# 20ma.net
KiCad netlist of a schematic drawn in EAGLE
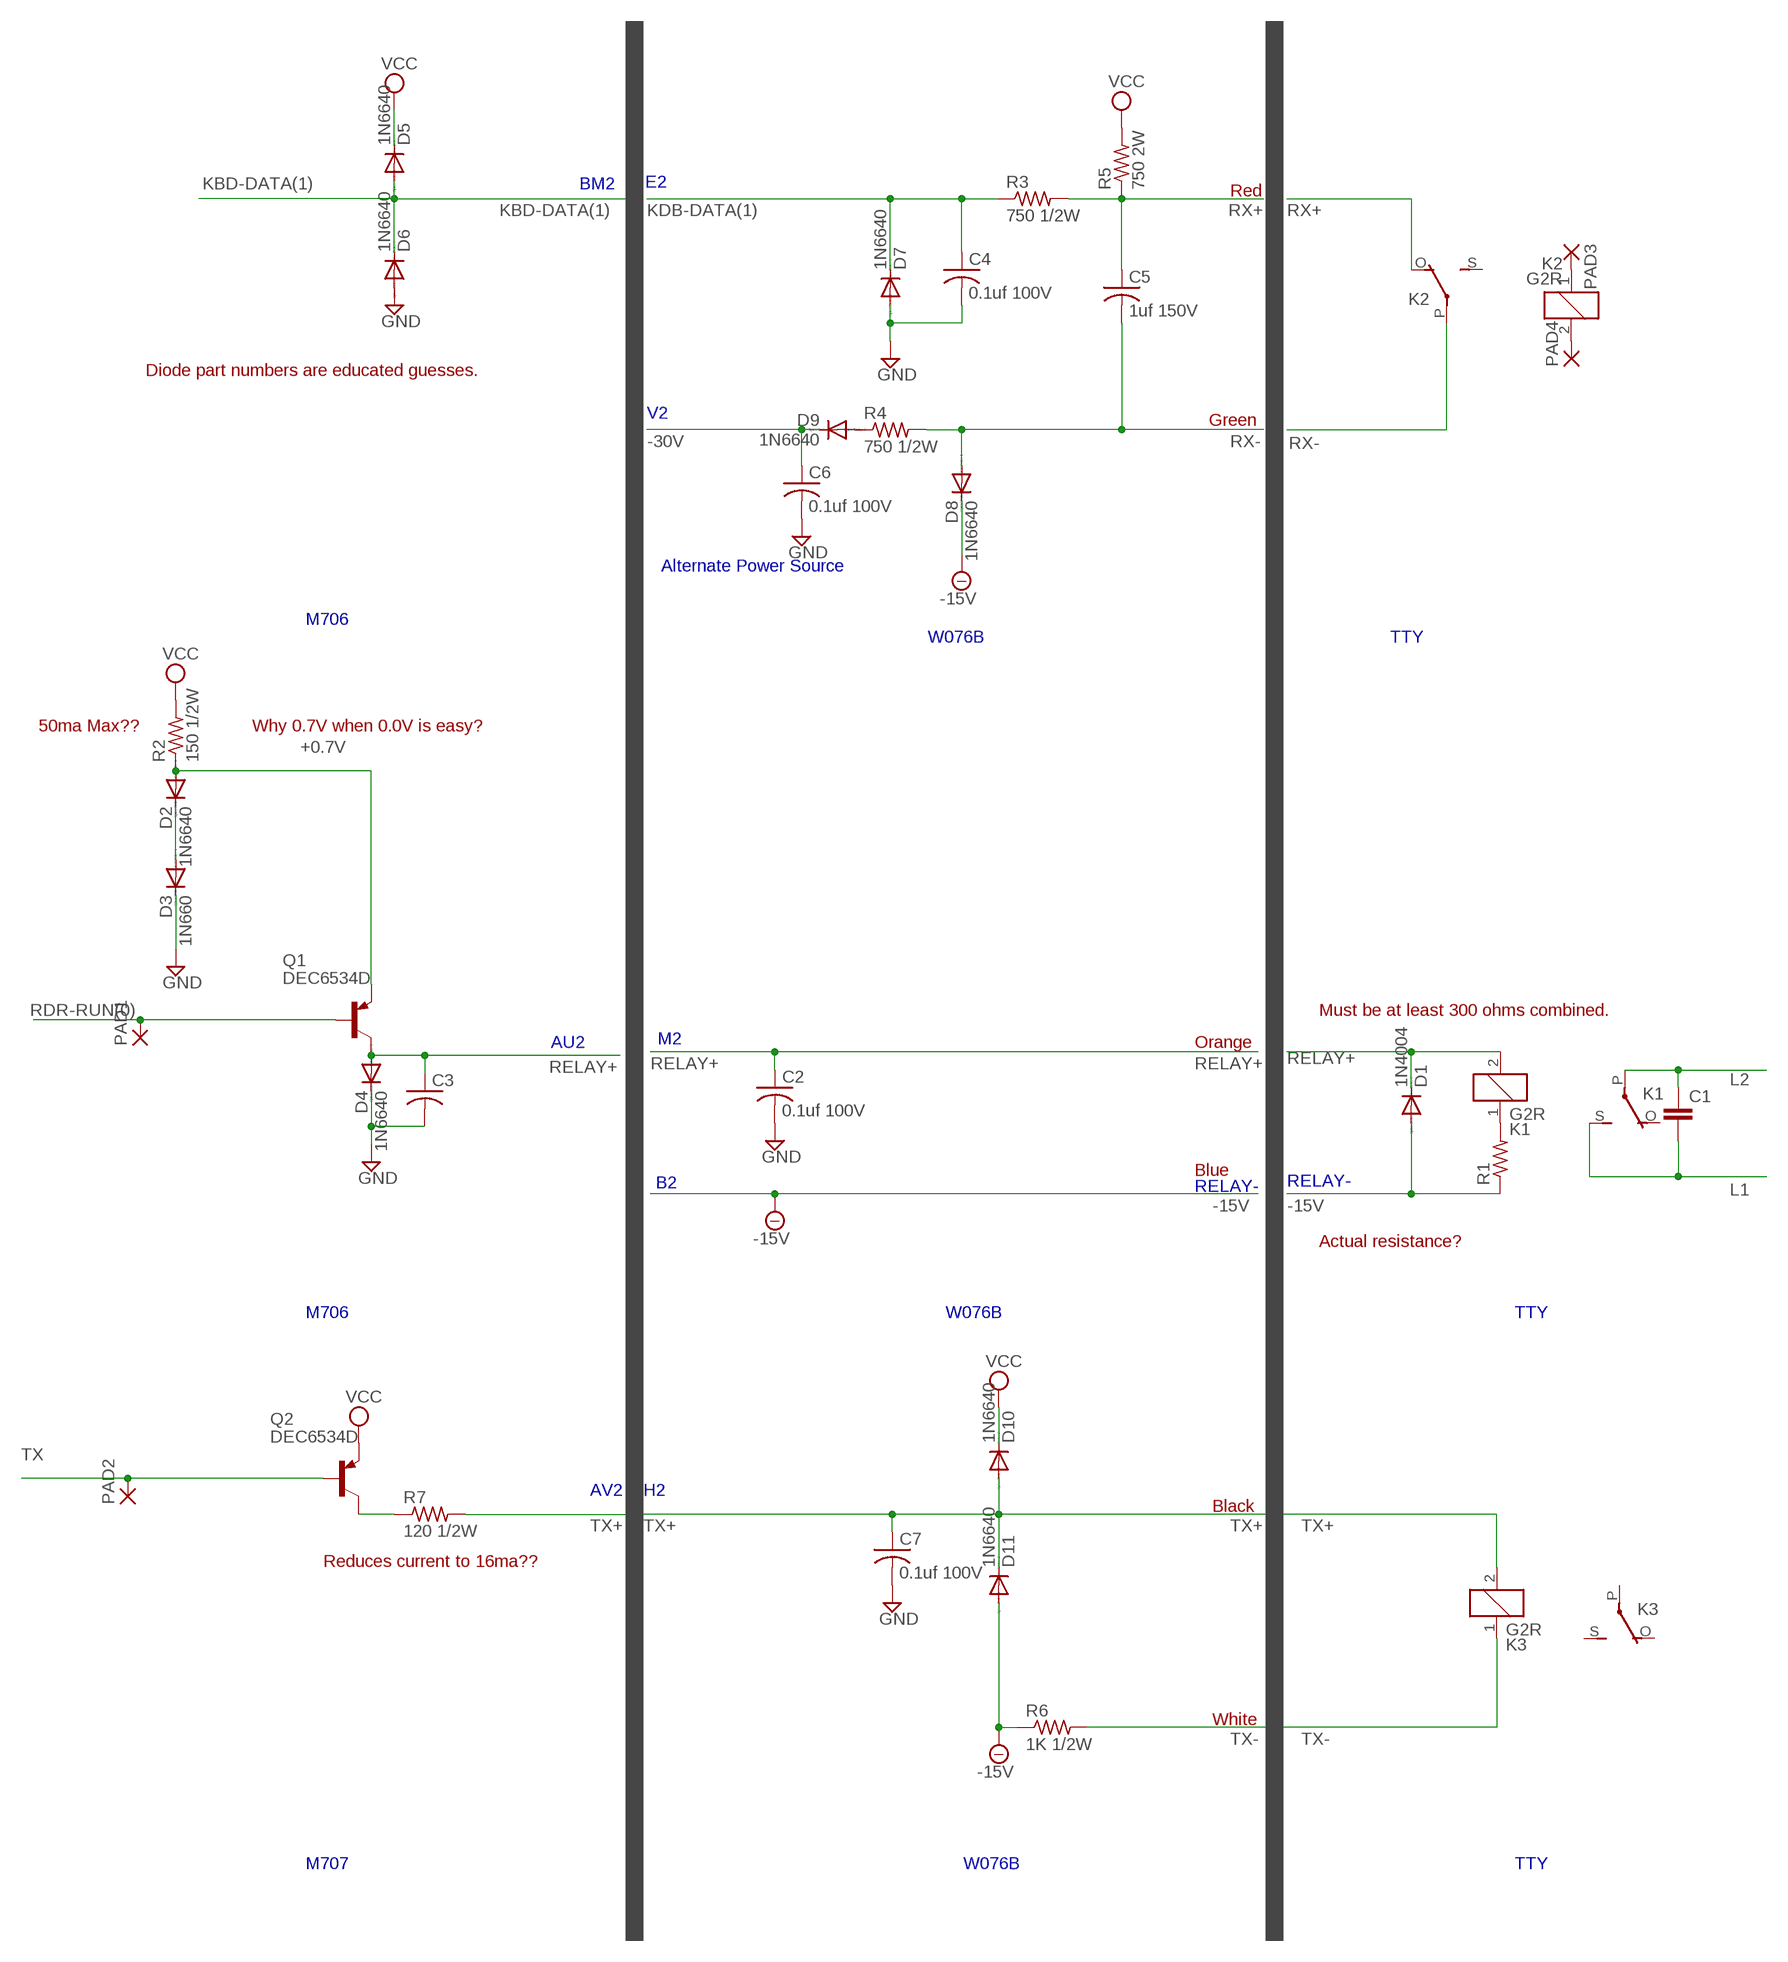
[diagram p0: schematic, sheet 1]

(export (version "E")
  (design (tool "Eeschema 10.0.6"))
  (components
    (comp (ref "C1")
      (value "C22/10")
      (footprint "eagle-import:C22.5B10")
      (libsource (lib "eagle-import") (part "C22/10"))
    )
    (comp (ref "C2")
      (value "0.1uf 100V")
      (footprint "eagle-import:C025-025X050")
      (libsource (lib "eagle-import") (part "C-US025-025X050"))
    )
    (comp (ref "C3")
      (value "C-US025-025X050")
      (footprint "eagle-import:C025-025X050")
      (libsource (lib "eagle-import") (part "C-US025-025X050"))
    )
    (comp (ref "C4")
      (value "0.1uf 100V")
      (footprint "eagle-import:C025-025X050")
      (libsource (lib "eagle-import") (part "C-US025-025X050"))
    )
    (comp (ref "C5")
      (value "1uf 150V")
      (footprint "eagle-import:C075-063X106")
      (libsource (lib "eagle-import") (part "C-US075-063X106"))
    )
    (comp (ref "C6")
      (value "0.1uf 100V")
      (footprint "eagle-import:C025-025X050")
      (libsource (lib "eagle-import") (part "C-US025-025X050"))
    )
    (comp (ref "C7")
      (value "0.1uf 100V")
      (footprint "eagle-import:C025-025X050")
      (libsource (lib "eagle-import") (part "C-US025-025X050"))
    )
    (comp (ref "D1")
      (value "1N4004")
      (footprint "eagle-import:DO41-10")
      (libsource (lib "eagle-import") (part "1N4004"))
    )
    (comp (ref "D2")
      (value "1N6640")
      (footprint "eagle-import:DO41-10")
      (libsource (lib "eagle-import") (part "1N4004"))
    )
    (comp (ref "D3")
      (value "1N660")
      (footprint "eagle-import:DO41-10")
      (libsource (lib "eagle-import") (part "1N4004"))
    )
    (comp (ref "D4")
      (value "1N6640")
      (footprint "eagle-import:DO41-10")
      (libsource (lib "eagle-import") (part "1N4004"))
    )
    (comp (ref "D5")
      (value "1N6640")
      (footprint "eagle-import:DO41-10")
      (libsource (lib "eagle-import") (part "1N4004"))
    )
    (comp (ref "D6")
      (value "1N6640")
      (footprint "eagle-import:DO41-10")
      (libsource (lib "eagle-import") (part "1N4004"))
    )
    (comp (ref "D7")
      (value "1N6640")
      (footprint "eagle-import:DO41-10")
      (libsource (lib "eagle-import") (part "1N4004"))
    )
    (comp (ref "D8")
      (value "1N6640")
      (footprint "eagle-import:DO41-10")
      (libsource (lib "eagle-import") (part "1N4004"))
    )
    (comp (ref "D9")
      (value "1N6640")
      (footprint "eagle-import:DO41-10")
      (libsource (lib "eagle-import") (part "1N4004"))
    )
    (comp (ref "D10")
      (value "1N6640")
      (footprint "eagle-import:DO41-10")
      (libsource (lib "eagle-import") (part "1N4004"))
    )
    (comp (ref "D11")
      (value "1N6640")
      (footprint "eagle-import:DO41-10")
      (libsource (lib "eagle-import") (part "1N4004"))
    )
    (comp (ref "K1")
      (value "G2R")
      (footprint "eagle-import:G2R")
      (libsource (lib "eagle-import") (part "G2R"))
    )
    (comp (ref "K2")
      (value "G2R")
      (footprint "eagle-import:G2R")
      (libsource (lib "eagle-import") (part "G2R"))
    )
    (comp (ref "K3")
      (value "G2R")
      (footprint "eagle-import:G2R")
      (libsource (lib "eagle-import") (part "G2R"))
    )
    (comp (ref "PAD1")
      (value "1,6/0,8")
      (footprint "eagle-import:1,6_0,8")
      (libsource (lib "eagle-import") (part "1,6/0,8"))
    )
    (comp (ref "PAD2")
      (value "1,6/0,8")
      (footprint "eagle-import:1,6_0,8")
      (libsource (lib "eagle-import") (part "1,6/0,8"))
    )
    (comp (ref "PAD3")
      (value "1,6/0,8")
      (footprint "eagle-import:1,6_0,8")
      (libsource (lib "eagle-import") (part "1,6/0,8"))
    )
    (comp (ref "PAD4")
      (value "1,6/0,8")
      (footprint "eagle-import:1,6_0,8")
      (libsource (lib "eagle-import") (part "1,6/0,8"))
    )
    (comp (ref "Q1")
      (value "DEC6534D")
      (footprint "eagle-import:TO92")
      (libsource (lib "eagle-import") (part "2N3906"))
    )
    (comp (ref "Q2")
      (value "DEC6534D")
      (footprint "eagle-import:TO92")
      (libsource (lib "eagle-import") (part "2N3906"))
    )
    (comp (ref "R1")
      (value "R-US_0309/12")
      (footprint "eagle-import:0309_12")
      (libsource (lib "eagle-import") (part "R-US_0309/12"))
    )
    (comp (ref "R2")
      (value "150 1/2W")
      (footprint "eagle-import:0207_10")
      (libsource (lib "eagle-import") (part "R-US_0207/10"))
    )
    (comp (ref "R3")
      (value "750 1/2W")
      (footprint "eagle-import:0309_12")
      (libsource (lib "eagle-import") (part "R-US_0309/12"))
    )
    (comp (ref "R4")
      (value "750 1/2W")
      (footprint "eagle-import:0309_12")
      (libsource (lib "eagle-import") (part "R-US_0309/12"))
    )
    (comp (ref "R5")
      (value "750 2W")
      (footprint "eagle-import:0309_12")
      (libsource (lib "eagle-import") (part "R-US_0309/12"))
    )
    (comp (ref "R6")
      (value "1K 1/2W")
      (footprint "eagle-import:0309_12")
      (libsource (lib "eagle-import") (part "R-US_0309/12"))
    )
    (comp (ref "R7")
      (value "120 1/2W")
      (footprint "eagle-import:0309_12")
      (libsource (lib "eagle-import") (part "R-US_0309/12"))
    )
  )
  (nets
    (net (code "1") (name "-15V") (class "Default")
      (node (ref "D1") (pin "A") (pinfunction "A_A") (pintype "passive"))
      (node (ref "D11") (pin "A") (pinfunction "A_A") (pintype "passive"))
      (node (ref "D8") (pin "C") (pinfunction "C_C") (pintype "passive"))
      (node (ref "R1") (pin "1") (pinfunction "1_1") (pintype "passive"))
      (node (ref "R6") (pin "1") (pinfunction "1_1") (pintype "passive"))
    )
    (net (code "2") (name "/+0.7V") (class "Default")
      (node (ref "D2") (pin "A") (pinfunction "A_A") (pintype "passive"))
      (node (ref "Q1") (pin "3") (pinfunction "E_3") (pintype "passive"))
      (node (ref "R2") (pin "1") (pinfunction "1_1") (pintype "passive"))
    )
    (net (code "3") (name "/-30V") (class "Default")
      (node (ref "C6") (pin "1") (pinfunction "1_1") (pintype "passive"))
      (node (ref "D9") (pin "C") (pinfunction "C_C") (pintype "passive"))
    )
    (net (code "4") (name "/KBD-DATA(1)") (class "Default")
      (node (ref "D5") (pin "A") (pinfunction "A_A") (pintype "passive"))
      (node (ref "D6") (pin "C") (pinfunction "C_C") (pintype "passive"))
    )
    (net (code "5") (name "/KDB-DATA(1)") (class "Default")
      (node (ref "C4") (pin "1") (pinfunction "1_1") (pintype "passive"))
      (node (ref "D7") (pin "C") (pinfunction "C_C") (pintype "passive"))
      (node (ref "R3") (pin "1") (pinfunction "1_1") (pintype "passive"))
    )
    (net (code "6") (name "/L1") (class "Default")
      (node (ref "C1") (pin "2") (pinfunction "2_2") (pintype "passive"))
      (node (ref "K1") (pin "S") (pinfunction "S_S") (pintype "passive"))
    )
    (net (code "7") (name "/L2") (class "Default")
      (node (ref "C1") (pin "1") (pinfunction "1_1") (pintype "passive"))
      (node (ref "K1") (pin "P") (pinfunction "P_P") (pintype "passive"))
    )
    (net (code "8") (name "/RDR-RUN(0)") (class "Default")
      (node (ref "PAD1") (pin "1") (pinfunction "P_1") (pintype "passive"))
      (node (ref "Q1") (pin "2") (pinfunction "B_2") (pintype "passive"))
    )
    (net (code "9") (name "/RELAY+") (class "Default")
      (node (ref "C2") (pin "1") (pinfunction "1_1") (pintype "passive"))
      (node (ref "C3") (pin "1") (pinfunction "1_1") (pintype "passive"))
      (node (ref "D1") (pin "C") (pinfunction "C_C") (pintype "passive"))
      (node (ref "D4") (pin "A") (pinfunction "A_A") (pintype "passive"))
      (node (ref "K1") (pin "2") (pinfunction "2_2") (pintype "passive"))
      (node (ref "Q1") (pin "1") (pinfunction "C_1") (pintype "passive"))
    )
    (net (code "10") (name "/RX+") (class "Default")
      (node (ref "C5") (pin "1") (pinfunction "1_1") (pintype "passive"))
      (node (ref "K2") (pin "O") (pinfunction "O_O") (pintype "passive"))
      (node (ref "R3") (pin "2") (pinfunction "2_2") (pintype "passive"))
      (node (ref "R5") (pin "1") (pinfunction "1_1") (pintype "passive"))
    )
    (net (code "11") (name "/RX-") (class "Default")
      (node (ref "C5") (pin "2") (pinfunction "2_2") (pintype "passive"))
      (node (ref "D8") (pin "A") (pinfunction "A_A") (pintype "passive"))
      (node (ref "K2") (pin "P") (pinfunction "P_P") (pintype "passive"))
      (node (ref "R4") (pin "2") (pinfunction "2_2") (pintype "passive"))
    )
    (net (code "12") (name "/TX") (class "Default")
      (node (ref "PAD2") (pin "1") (pinfunction "P_1") (pintype "passive"))
      (node (ref "Q2") (pin "2") (pinfunction "B_2") (pintype "passive"))
    )
    (net (code "13") (name "/TX+") (class "Default")
      (node (ref "C7") (pin "1") (pinfunction "1_1") (pintype "passive"))
      (node (ref "D10") (pin "A") (pinfunction "A_A") (pintype "passive"))
      (node (ref "D11") (pin "C") (pinfunction "C_C") (pintype "passive"))
      (node (ref "K3") (pin "2") (pinfunction "2_2") (pintype "passive"))
      (node (ref "R7") (pin "2") (pinfunction "2_2") (pintype "passive"))
    )
    (net (code "14") (name "/TX-") (class "Default")
      (node (ref "K3") (pin "1") (pinfunction "1_1") (pintype "passive"))
      (node (ref "R6") (pin "2") (pinfunction "2_2") (pintype "passive"))
    )
    (net (code "15") (name "GND") (class "Default")
      (node (ref "C2") (pin "2") (pinfunction "2_2") (pintype "passive"))
      (node (ref "C3") (pin "2") (pinfunction "2_2") (pintype "passive"))
      (node (ref "C4") (pin "2") (pinfunction "2_2") (pintype "passive"))
      (node (ref "C6") (pin "2") (pinfunction "2_2") (pintype "passive"))
      (node (ref "C7") (pin "2") (pinfunction "2_2") (pintype "passive"))
      (node (ref "D3") (pin "C") (pinfunction "C_C") (pintype "passive"))
      (node (ref "D4") (pin "C") (pinfunction "C_C") (pintype "passive"))
      (node (ref "D6") (pin "A") (pinfunction "A_A") (pintype "passive"))
      (node (ref "D7") (pin "A") (pinfunction "A_A") (pintype "passive"))
    )
    (net (code "16") (name "Net-(D2-PadC)") (class "Default")
      (node (ref "D2") (pin "C") (pinfunction "C_C") (pintype "passive"))
      (node (ref "D3") (pin "A") (pinfunction "A_A") (pintype "passive"))
    )
    (net (code "17") (name "Net-(D9-PadA)") (class "Default")
      (node (ref "D9") (pin "A") (pinfunction "A_A") (pintype "passive"))
      (node (ref "R4") (pin "1") (pinfunction "1_1") (pintype "passive"))
    )
    (net (code "18") (name "Net-(K1-Pad1)") (class "Default")
      (node (ref "K1") (pin "1") (pinfunction "1_1") (pintype "passive"))
      (node (ref "R1") (pin "2") (pinfunction "2_2") (pintype "passive"))
    )
    (net (code "19") (name "Net-(PAD3-P)") (class "Default")
      (node (ref "K2") (pin "1") (pinfunction "1_1") (pintype "passive"))
      (node (ref "PAD3") (pin "1") (pinfunction "P_1") (pintype "passive"))
    )
    (net (code "20") (name "Net-(PAD4-P)") (class "Default")
      (node (ref "K2") (pin "2") (pinfunction "2_2") (pintype "passive"))
      (node (ref "PAD4") (pin "1") (pinfunction "P_1") (pintype "passive"))
    )
    (net (code "21") (name "Net-(Q2-C)") (class "Default")
      (node (ref "Q2") (pin "1") (pinfunction "C_1") (pintype "passive"))
      (node (ref "R7") (pin "1") (pinfunction "1_1") (pintype "passive"))
    )
    (net (code "22") (name "VCC") (class "Default")
      (node (ref "D10") (pin "C") (pinfunction "C_C") (pintype "passive"))
      (node (ref "D5") (pin "C") (pinfunction "C_C") (pintype "passive"))
      (node (ref "Q2") (pin "3") (pinfunction "E_3") (pintype "passive"))
      (node (ref "R2") (pin "2") (pinfunction "2_2") (pintype "passive"))
      (node (ref "R5") (pin "2") (pinfunction "2_2") (pintype "passive"))
    )
    (net (code "23") (name "unconnected-(K1-PadO)") (class "Default")
      (node (ref "K1") (pin "O") (pinfunction "O_O") (pintype "passive"))
    )
    (net (code "24") (name "unconnected-(K2-PadS)") (class "Default")
      (node (ref "K2") (pin "S") (pinfunction "S_S") (pintype "passive"))
    )
    (net (code "25") (name "unconnected-(K3-PadO)") (class "Default")
      (node (ref "K3") (pin "O") (pinfunction "O_O") (pintype "passive"))
    )
    (net (code "26") (name "unconnected-(K3-PadP)") (class "Default")
      (node (ref "K3") (pin "P") (pinfunction "P_P") (pintype "passive"))
    )
    (net (code "27") (name "unconnected-(K3-PadS)") (class "Default")
      (node (ref "K3") (pin "S") (pinfunction "S_S") (pintype "passive"))
    )
  )
)
